# wifi-adapter.net
KiCad netlist of a schematic drawn in EAGLE
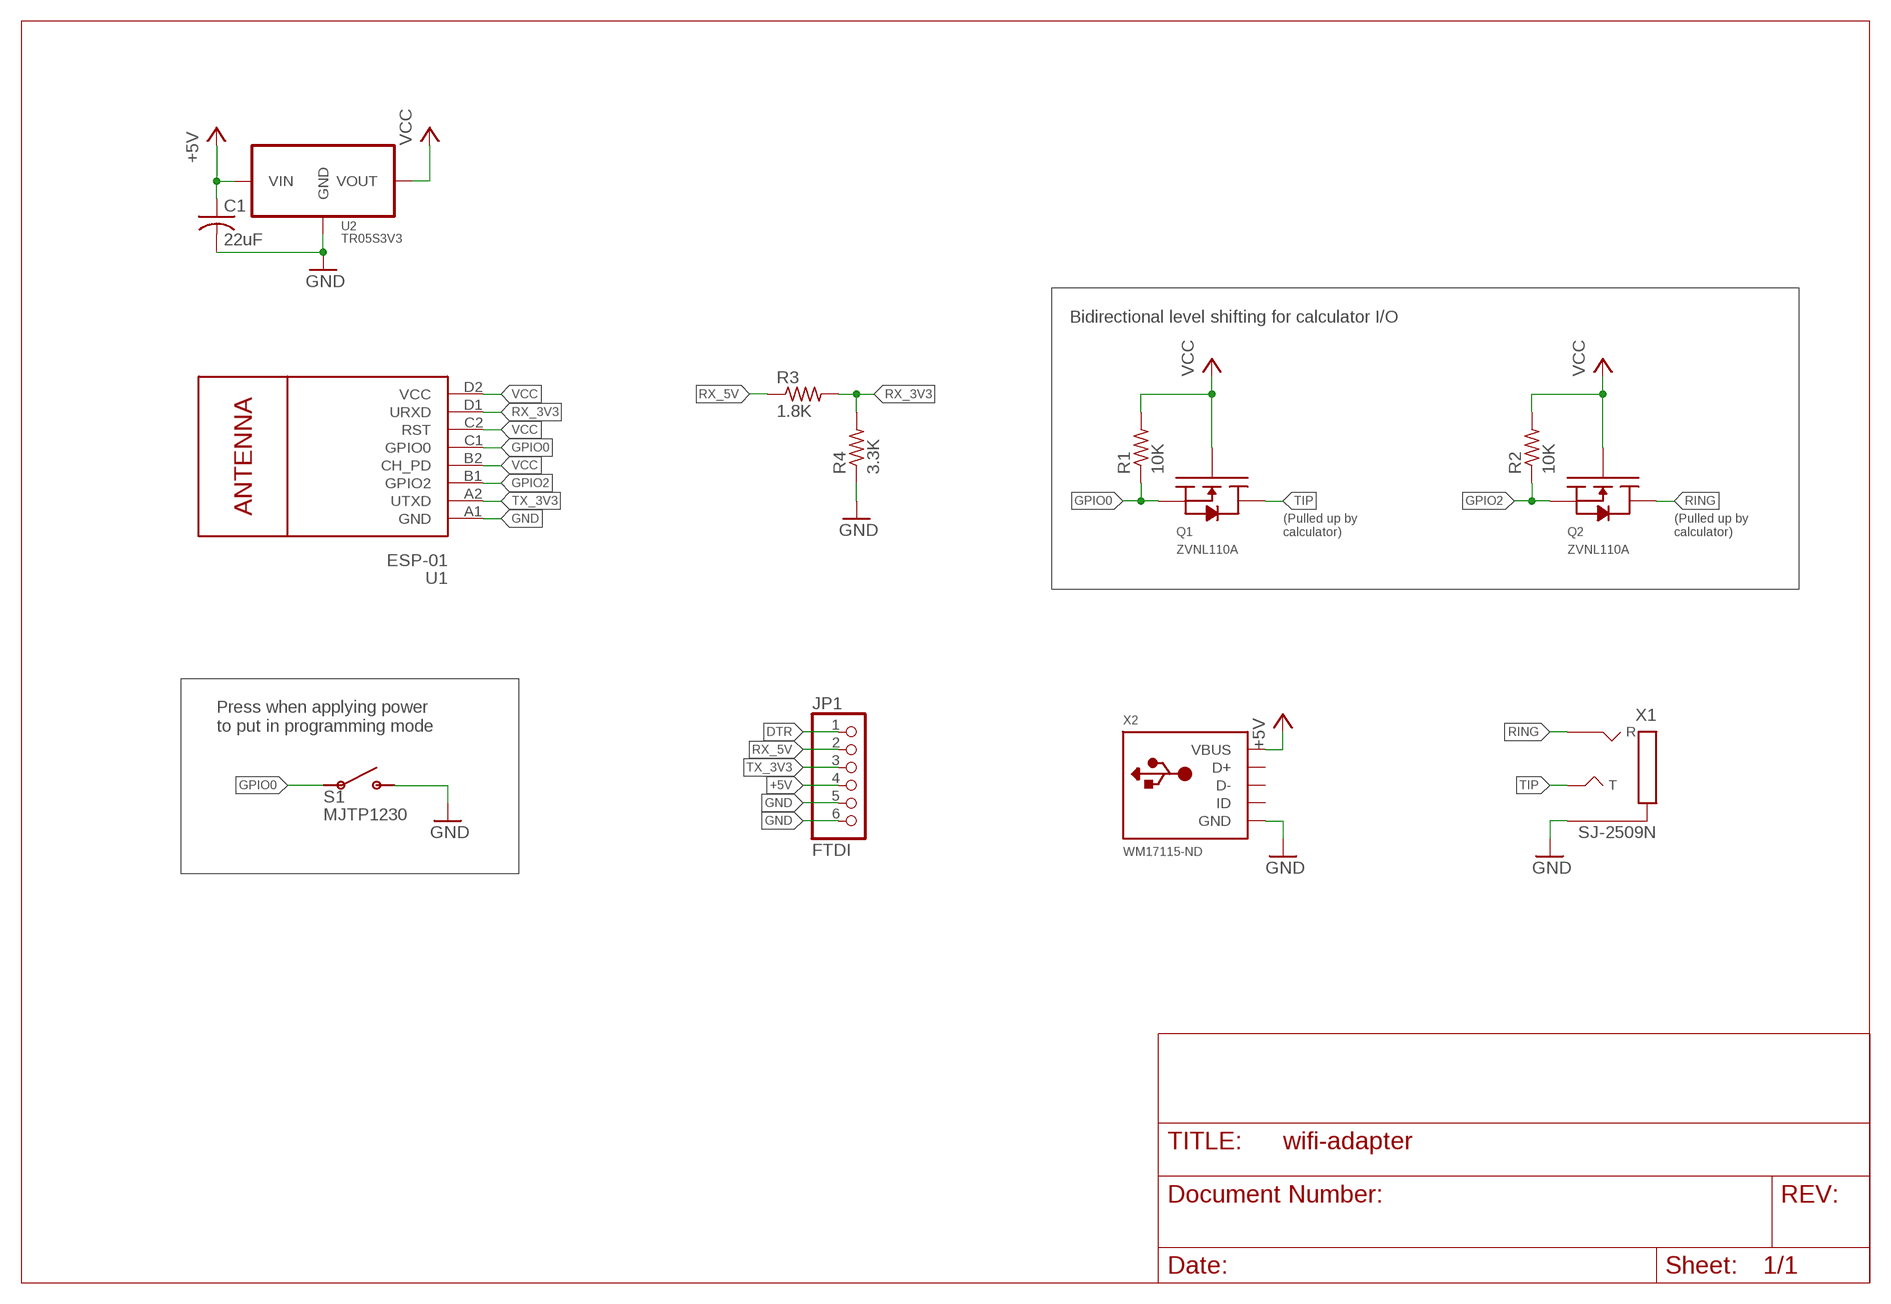
[diagram p0: schematic, sheet 1]

(export (version "E")
  (design (tool "Eeschema 10.0.6"))
  (components
    (comp (ref "C1")
      (value "22uF")
      (footprint "eagle-import:C025-025X050")
      (libsource (lib "eagle-import") (part "C-US025-025X050"))
    )
    (comp (ref "JP1")
      (value "FTDI")
      (footprint "eagle-import:1X06")
      (libsource (lib "eagle-import") (part "PINHD-1X6"))
    )
    (comp (ref "Q1")
      (value "ZVNL110A")
      (footprint "eagle-import:E-LINE-RA")
      (libsource (lib "eagle-import") (part "ZVNL110ARIGHTANGLE"))
    )
    (comp (ref "Q2")
      (value "ZVNL110A")
      (footprint "eagle-import:E-LINE-RA")
      (libsource (lib "eagle-import") (part "ZVNL110ARIGHTANGLE"))
    )
    (comp (ref "R1")
      (value "10K")
      (footprint "eagle-import:0207_10")
      (libsource (lib "eagle-import") (part "R-US_0207/10"))
    )
    (comp (ref "R2")
      (value "10K")
      (footprint "eagle-import:0207_10")
      (libsource (lib "eagle-import") (part "R-US_0207/10"))
    )
    (comp (ref "R3")
      (value "1.8K")
      (footprint "eagle-import:0207_10")
      (libsource (lib "eagle-import") (part "R-US_0207/10"))
    )
    (comp (ref "R4")
      (value "3.3K")
      (footprint "eagle-import:0207_10")
      (libsource (lib "eagle-import") (part "R-US_0207/10"))
    )
    (comp (ref "S1")
      (value "MJTP1230")
      (footprint "eagle-import:TACTILE-BUTTON-MJTP1230")
      (libsource (lib "eagle-import") (part "TACTILE-BUTTON-MJTP1230"))
    )
    (comp (ref "U1")
      (value "ESP-01")
      (footprint "eagle-import:WIRELESS-WIFI-ESP-01")
      (libsource (lib "eagle-import") (part "WIRELESS-WIFI-ESP-01"))
    )
    (comp (ref "U2")
      (value "TR05S3V3")
      (footprint "eagle-import:3-SIP")
      (libsource (lib "eagle-import") (part "TR05SXX"))
    )
    (comp (ref "X1")
      (value "SJ-2509N")
      (footprint "eagle-import:SJ-2509N")
      (libsource (lib "eagle-import") (part "SJ-2509N"))
    )
    (comp (ref "X2")
      (value "WM17115-ND")
      (footprint "eagle-import:USB-MINI-B")
      (libsource (lib "eagle-import") (part "USB-MINI-B"))
    )
  )
  (nets
    (net (code "1") (name "+5V") (class "Default")
      (node (ref "C1") (pin "1") (pinfunction "1_1") (pintype "passive"))
      (node (ref "JP1") (pin "4") (pinfunction "4_4") (pintype "passive"))
      (node (ref "U2") (pin "P$1") (pinfunction "VIN_P$1") (pintype "input"))
      (node (ref "X2") (pin "VBUS") (pinfunction "VBUS_VBUS") (pintype "power_in"))
    )
    (net (code "2") (name "DTR") (class "Default")
      (node (ref "JP1") (pin "1") (pinfunction "1_1") (pintype "passive"))
    )
    (net (code "3") (name "GND") (class "Default")
      (node (ref "C1") (pin "2") (pinfunction "2_2") (pintype "passive"))
      (node (ref "JP1") (pin "5") (pinfunction "5_5") (pintype "passive"))
      (node (ref "JP1") (pin "6") (pinfunction "6_6") (pintype "passive"))
      (node (ref "R4") (pin "1") (pinfunction "1_1") (pintype "passive"))
      (node (ref "S1") (pin "P$2") (pinfunction "3_P$2") (pintype "passive"))
      (node (ref "S1") (pin "P$4") (pinfunction "3_P$4") (pintype "passive"))
      (node (ref "U1") (pin "A1") (pinfunction "GND_A1") (pintype "power_in"))
      (node (ref "U2") (pin "P$2") (pinfunction "GND_P$2") (pintype "power_in"))
      (node (ref "X1") (pin "P$1") (pinfunction "P$1_P$1") (pintype "power_in"))
      (node (ref "X2") (pin "GND") (pinfunction "GND_GND") (pintype "power_in"))
      (node (ref "X2") (pin "GND1") (pinfunction "GND_GND1") (pintype "power_in"))
      (node (ref "X2") (pin "GND4") (pinfunction "GND_GND4") (pintype "power_in"))
    )
    (net (code "4") (name "GPIO0") (class "Default")
      (node (ref "Q1") (pin "P$3") (pinfunction "S_P$3") (pintype "bidirectional"))
      (node (ref "R1") (pin "1") (pinfunction "1_1") (pintype "passive"))
      (node (ref "S1") (pin "P$1") (pinfunction "1_P$1") (pintype "passive"))
      (node (ref "S1") (pin "P$3") (pinfunction "1_P$3") (pintype "passive"))
      (node (ref "U1") (pin "C1") (pinfunction "GPIO0_C1") (pintype "bidirectional"))
    )
    (net (code "5") (name "GPIO2") (class "Default")
      (node (ref "Q2") (pin "P$3") (pinfunction "S_P$3") (pintype "bidirectional"))
      (node (ref "R2") (pin "1") (pinfunction "1_1") (pintype "passive"))
      (node (ref "U1") (pin "B1") (pinfunction "GPIO2_B1") (pintype "bidirectional"))
    )
    (net (code "6") (name "RING") (class "Default")
      (node (ref "Q2") (pin "P$1") (pinfunction "D_P$1") (pintype "bidirectional"))
      (node (ref "X1") (pin "P$2") (pinfunction "P$2_P$2") (pintype "bidirectional"))
    )
    (net (code "7") (name "RX_3V3") (class "Default")
      (node (ref "R3") (pin "2") (pinfunction "2_2") (pintype "passive"))
      (node (ref "R4") (pin "2") (pinfunction "2_2") (pintype "passive"))
      (node (ref "U1") (pin "D1") (pinfunction "URXD_D1") (pintype "bidirectional"))
    )
    (net (code "8") (name "RX_5V") (class "Default")
      (node (ref "JP1") (pin "2") (pinfunction "2_2") (pintype "passive"))
      (node (ref "R3") (pin "1") (pinfunction "1_1") (pintype "passive"))
    )
    (net (code "9") (name "TIP") (class "Default")
      (node (ref "Q1") (pin "P$1") (pinfunction "D_P$1") (pintype "bidirectional"))
      (node (ref "X1") (pin "P$3") (pinfunction "P$3_P$3") (pintype "bidirectional"))
    )
    (net (code "10") (name "TX_3V3") (class "Default")
      (node (ref "JP1") (pin "3") (pinfunction "3_3") (pintype "passive"))
      (node (ref "U1") (pin "A2") (pinfunction "UTXD_A2") (pintype "bidirectional"))
    )
    (net (code "11") (name "VCC") (class "Default")
      (node (ref "Q1") (pin "P$2") (pinfunction "G_P$2") (pintype "bidirectional"))
      (node (ref "Q2") (pin "P$2") (pinfunction "G_P$2") (pintype "bidirectional"))
      (node (ref "R1") (pin "2") (pinfunction "2_2") (pintype "passive"))
      (node (ref "R2") (pin "2") (pinfunction "2_2") (pintype "passive"))
      (node (ref "U1") (pin "B2") (pinfunction "CH_PD_B2") (pintype "bidirectional"))
      (node (ref "U1") (pin "C2") (pinfunction "RST_C2") (pintype "bidirectional"))
      (node (ref "U1") (pin "D2") (pinfunction "VCC_D2") (pintype "power_in"))
      (node (ref "U2") (pin "P$3") (pinfunction "VOUT_P$3") (pintype "output"))
    )
    (net (code "12") (name "unconnected-(X2-PadD+)") (class "Default")
      (node (ref "X2") (pin "D+") (pinfunction "D+_D+") (pintype "bidirectional"))
    )
    (net (code "13") (name "unconnected-(X2-PadD-)") (class "Default")
      (node (ref "X2") (pin "D-") (pinfunction "D-_D-") (pintype "bidirectional"))
    )
    (net (code "14") (name "unconnected-(X2-PadID)") (class "Default")
      (node (ref "X2") (pin "ID") (pinfunction "ID_ID") (pintype "bidirectional"))
    )
  )
)
